# isolator.net
KiCad netlist of a schematic drawn in EAGLE
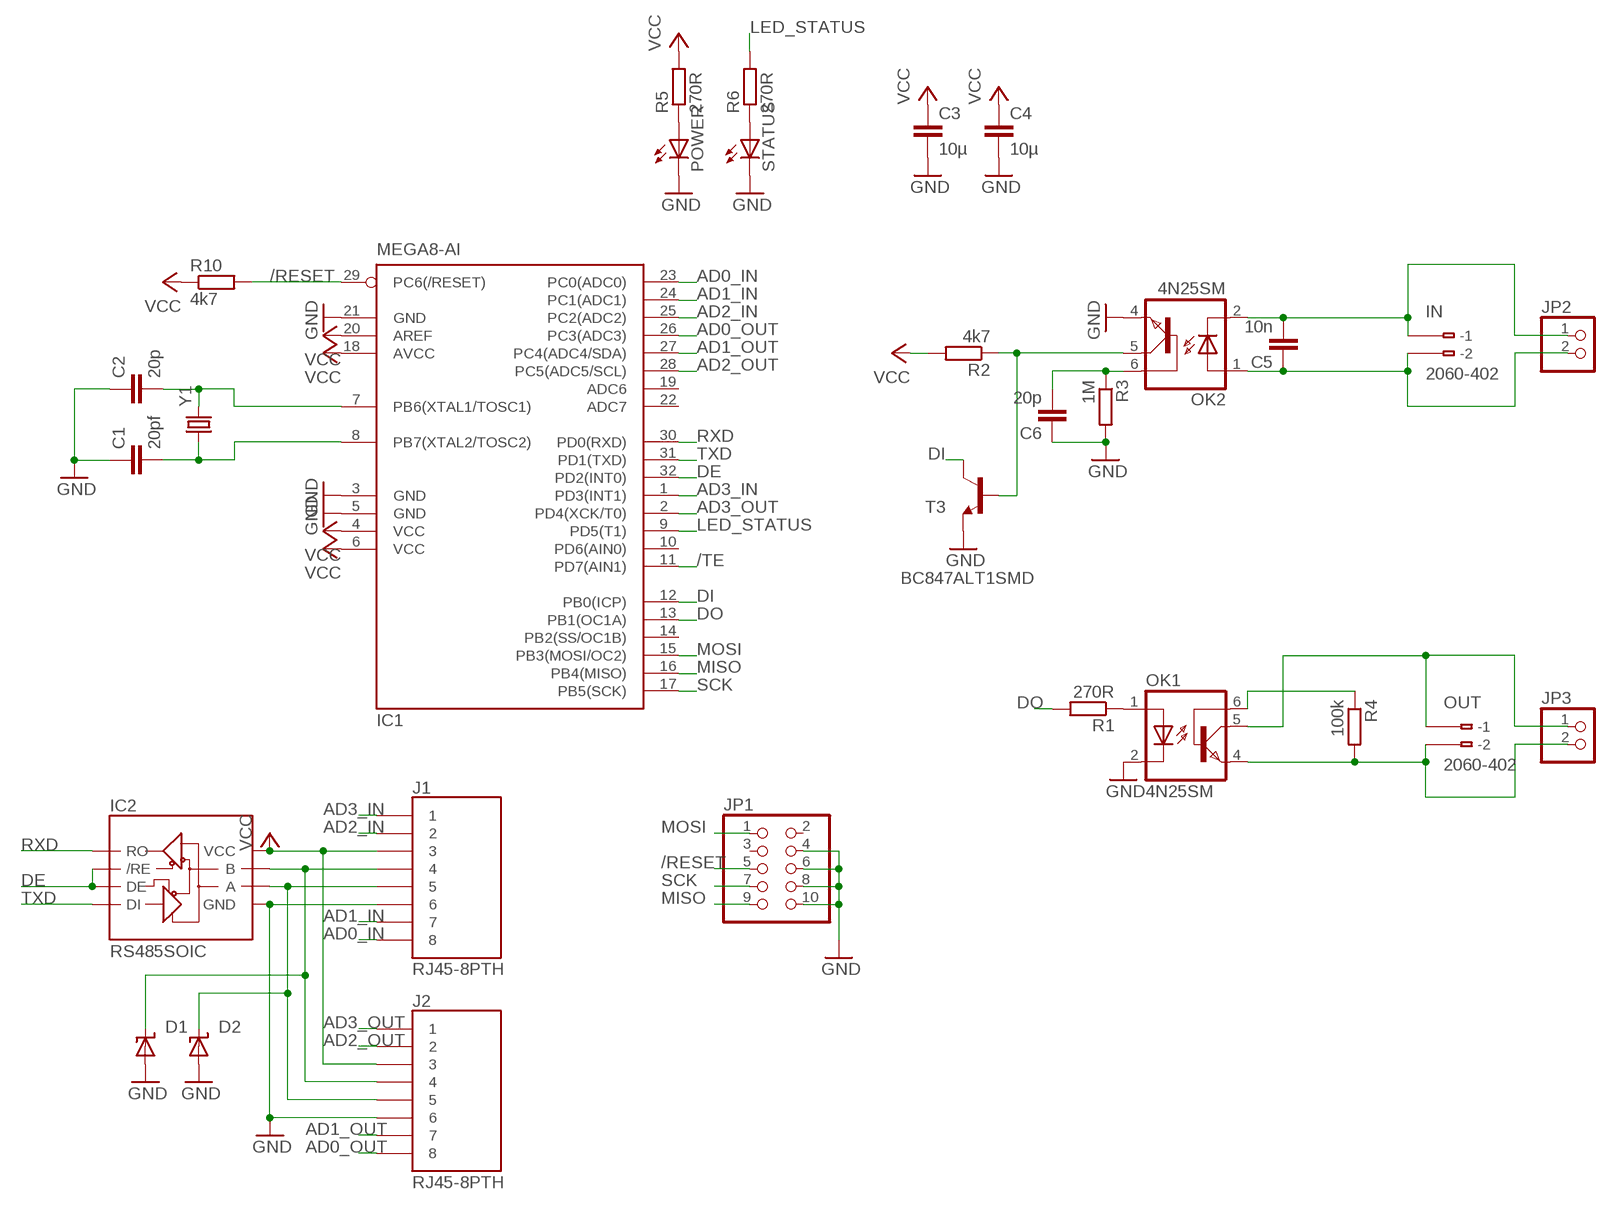
[diagram p0: schematic, sheet 1]

(export (version "E")
  (design (tool "Eeschema 10.0.6"))
  (components
    (comp (ref "C1")
      (value "20pf")
      (footprint "eagle-import:C0805")
      (libsource (lib "eagle-import") (part "C-EUC0805"))
    )
    (comp (ref "C2")
      (value "20p")
      (footprint "eagle-import:C0805")
      (libsource (lib "eagle-import") (part "C-EUC0805"))
    )
    (comp (ref "C3")
      (value "10µ")
      (footprint "eagle-import:C0805")
      (libsource (lib "eagle-import") (part "C-EUC0805"))
    )
    (comp (ref "C4")
      (value "10µ")
      (footprint "eagle-import:C0805")
      (libsource (lib "eagle-import") (part "C-EUC0805"))
    )
    (comp (ref "C5")
      (value "10n")
      (footprint "eagle-import:C0805")
      (libsource (lib "eagle-import") (part "C-EUC0805"))
    )
    (comp (ref "C6")
      (value "20p")
      (footprint "eagle-import:C0805")
      (libsource (lib "eagle-import") (part "C-EUC0805"))
    )
    (comp (ref "D1")
      (value "SUPPRESSOR-SMBJ")
      (footprint "eagle-import:SMBJ")
      (libsource (lib "eagle-import") (part "SUPPRESSOR-SMBJ"))
    )
    (comp (ref "D2")
      (value "SUPPRESSOR-SMBJ")
      (footprint "eagle-import:SMBJ")
      (libsource (lib "eagle-import") (part "SUPPRESSOR-SMBJ"))
    )
    (comp (ref "IC1")
      (value "MEGA8-AI")
      (footprint "eagle-import:TQFP32-08")
      (fields (field (name "MPN") "ATMEGA8-16AU"))
      (libsource (lib "eagle-import") (part "MEGA8-AI"))
    )
    (comp (ref "IC2")
      (value "RS485SOIC")
      (footprint "eagle-import:SO08")
      (libsource (lib "eagle-import") (part "RS485SOIC"))
    )
    (comp (ref "IN")
      (value "2060-402")
      (footprint "eagle-import:2060-402")
      (libsource (lib "eagle-import") (part "2060-402"))
    )
    (comp (ref "J1")
      (value "RJ45-8PTH")
      (footprint "eagle-import:RJ45-8")
      (libsource (lib "eagle-import") (part "RJ45-8PTH"))
    )
    (comp (ref "J2")
      (value "RJ45-8PTH")
      (footprint "eagle-import:RJ45-8")
      (libsource (lib "eagle-import") (part "RJ45-8PTH"))
    )
    (comp (ref "JP1")
      (value "PINHD-2X5")
      (footprint "eagle-import:2X05")
      (libsource (lib "eagle-import") (part "PINHD-2X5"))
    )
    (comp (ref "JP2")
      (value "PINHD-1X2")
      (footprint "eagle-import:1X02")
      (libsource (lib "eagle-import") (part "PINHD-1X2"))
    )
    (comp (ref "JP3")
      (value "PINHD-1X2")
      (footprint "eagle-import:1X02")
      (libsource (lib "eagle-import") (part "PINHD-1X2"))
    )
    (comp (ref "OK1")
      (value "4N25SM")
      (footprint "eagle-import:DIL6-SMD")
      (fields (field (name "MF") "FAIRCHILD SEMICONDUCTOR"))
      (libsource (lib "eagle-import") (part "4N?MS25"))
    )
    (comp (ref "OK2")
      (value "4N25SM")
      (footprint "eagle-import:DIL6-SMD")
      (fields (field (name "MF") "FAIRCHILD SEMICONDUCTOR"))
      (libsource (lib "eagle-import") (part "4N?MS25"))
    )
    (comp (ref "OUT")
      (value "2060-402")
      (footprint "eagle-import:2060-402")
      (libsource (lib "eagle-import") (part "2060-402"))
    )
    (comp (ref "POWER")
      (value "LEDCHIP-LED0805")
      (footprint "eagle-import:CHIP-LED0805")
      (libsource (lib "eagle-import") (part "LEDCHIP-LED0805"))
    )
    (comp (ref "R1")
      (value "270R")
      (footprint "eagle-import:M0805")
      (libsource (lib "eagle-import") (part "R-EU_M0805"))
    )
    (comp (ref "R2")
      (value "4k7")
      (footprint "eagle-import:M0805")
      (libsource (lib "eagle-import") (part "R-EU_M0805"))
    )
    (comp (ref "R3")
      (value "1M")
      (footprint "eagle-import:M0805")
      (libsource (lib "eagle-import") (part "R-EU_M0805"))
    )
    (comp (ref "R4")
      (value "100k")
      (footprint "eagle-import:M0805")
      (libsource (lib "eagle-import") (part "R-EU_M0805"))
    )
    (comp (ref "R5")
      (value "270R")
      (footprint "eagle-import:M0805")
      (libsource (lib "eagle-import") (part "R-EU_M0805"))
    )
    (comp (ref "R6")
      (value "270R")
      (footprint "eagle-import:M0805")
      (libsource (lib "eagle-import") (part "R-EU_M0805"))
    )
    (comp (ref "R10")
      (value "4k7")
      (footprint "eagle-import:M0805")
      (libsource (lib "eagle-import") (part "R-EU_M0805"))
    )
    (comp (ref "STATUS")
      (value "LEDCHIP-LED0805")
      (footprint "eagle-import:CHIP-LED0805")
      (libsource (lib "eagle-import") (part "LEDCHIP-LED0805"))
    )
    (comp (ref "T3")
      (value "BC847ALT1SMD")
      (footprint "eagle-import:SOT23")
      (libsource (lib "eagle-import") (part "BC847SMDALT1"))
    )
    (comp (ref "Y1")
      (value "CRYSTAL10.5X4.8")
      (footprint "eagle-import:CRYSTAL-SMD-10.5X4.8-2PIN")
      (libsource (lib "eagle-import") (part "CRYSTAL10.5X4.8"))
    )
  )
  (nets
    (net (code "1") (name "/AD0_IN") (class "Default")
      (node (ref "IC1") (pin "23") (pinfunction "PC0(ADC0)_23") (pintype "bidirectional"))
      (node (ref "J1") (pin "8") (pinfunction "8_8") (pintype "bidirectional"))
    )
    (net (code "2") (name "/AD0_OUT") (class "Default")
      (node (ref "IC1") (pin "26") (pinfunction "PC3(ADC3)_26") (pintype "bidirectional"))
      (node (ref "J2") (pin "8") (pinfunction "8_8") (pintype "bidirectional"))
    )
    (net (code "3") (name "/AD1_IN") (class "Default")
      (node (ref "IC1") (pin "24") (pinfunction "PC1(ADC1)_24") (pintype "bidirectional"))
      (node (ref "J1") (pin "7") (pinfunction "7_7") (pintype "bidirectional"))
    )
    (net (code "4") (name "/AD1_OUT") (class "Default")
      (node (ref "IC1") (pin "27") (pinfunction "PC4(ADC4/SDA)_27") (pintype "bidirectional"))
      (node (ref "J2") (pin "7") (pinfunction "7_7") (pintype "bidirectional"))
    )
    (net (code "5") (name "/AD2_IN") (class "Default")
      (node (ref "IC1") (pin "25") (pinfunction "PC2(ADC2)_25") (pintype "bidirectional"))
      (node (ref "J1") (pin "2") (pinfunction "2_2") (pintype "bidirectional"))
    )
    (net (code "6") (name "/AD2_OUT") (class "Default")
      (node (ref "IC1") (pin "28") (pinfunction "PC5(ADC5/SCL)_28") (pintype "bidirectional"))
      (node (ref "J2") (pin "2") (pinfunction "2_2") (pintype "bidirectional"))
    )
    (net (code "7") (name "/AD3_IN") (class "Default")
      (node (ref "IC1") (pin "1") (pinfunction "PD3(INT1)_1") (pintype "bidirectional"))
      (node (ref "J1") (pin "1") (pinfunction "1_1") (pintype "bidirectional"))
    )
    (net (code "8") (name "/AD3_OUT") (class "Default")
      (node (ref "IC1") (pin "2") (pinfunction "PD4(XCK/T0)_2") (pintype "bidirectional"))
      (node (ref "J2") (pin "1") (pinfunction "1_1") (pintype "bidirectional"))
    )
    (net (code "9") (name "/DE") (class "Default")
      (node (ref "IC1") (pin "32") (pinfunction "PD2(INT0)_32") (pintype "bidirectional"))
      (node (ref "IC2") (pin "2") (pinfunction "/RE_2") (pintype "bidirectional"))
      (node (ref "IC2") (pin "3") (pinfunction "DE_3") (pintype "bidirectional"))
    )
    (net (code "10") (name "/DI") (class "Default")
      (node (ref "IC1") (pin "12") (pinfunction "PB0(ICP)_12") (pintype "bidirectional"))
      (node (ref "T3") (pin "3") (pinfunction "C_3") (pintype "passive"))
    )
    (net (code "11") (name "/DO") (class "Default")
      (node (ref "IC1") (pin "13") (pinfunction "PB1(OC1A)_13") (pintype "bidirectional"))
      (node (ref "R1") (pin "2") (pinfunction "2_2") (pintype "passive"))
    )
    (net (code "12") (name "/LED_STATUS") (class "Default")
      (node (ref "IC1") (pin "9") (pinfunction "PD5(T1)_9") (pintype "bidirectional"))
      (node (ref "R6") (pin "2") (pinfunction "2_2") (pintype "passive"))
    )
    (net (code "13") (name "/MISO") (class "Default")
      (node (ref "IC1") (pin "16") (pinfunction "PB4(MISO)_16") (pintype "bidirectional"))
      (node (ref "JP1") (pin "9") (pinfunction "9_9") (pintype "passive"))
    )
    (net (code "14") (name "/MOSI") (class "Default")
      (node (ref "IC1") (pin "15") (pinfunction "PB3(MOSI/OC2)_15") (pintype "bidirectional"))
      (node (ref "JP1") (pin "1") (pinfunction "1_1") (pintype "passive"))
    )
    (net (code "15") (name "/RXD") (class "Default")
      (node (ref "IC1") (pin "30") (pinfunction "PD0(RXD)_30") (pintype "bidirectional"))
      (node (ref "IC2") (pin "1") (pinfunction "RO_1") (pintype "bidirectional"))
    )
    (net (code "16") (name "/SCK") (class "Default")
      (node (ref "IC1") (pin "17") (pinfunction "PB5(SCK)_17") (pintype "bidirectional"))
      (node (ref "JP1") (pin "7") (pinfunction "7_7") (pintype "passive"))
    )
    (net (code "17") (name "/TXD") (class "Default")
      (node (ref "IC1") (pin "31") (pinfunction "PD1(TXD)_31") (pintype "bidirectional"))
      (node (ref "IC2") (pin "4") (pinfunction "DI_4") (pintype "bidirectional"))
    )
    (net (code "18") (name "/{slash}RESET") (class "Default")
      (node (ref "IC1") (pin "29") (pinfunction "PC6(/RESET)_29") (pintype "bidirectional"))
      (node (ref "JP1") (pin "5") (pinfunction "5_5") (pintype "passive"))
      (node (ref "R10") (pin "2") (pinfunction "2_2") (pintype "passive"))
    )
    (net (code "19") (name "/{slash}TE") (class "Default")
      (node (ref "IC1") (pin "11") (pinfunction "PD7(AIN1)_11") (pintype "bidirectional"))
    )
    (net (code "20") (name "GND") (class "Default")
      (node (ref "C1") (pin "1") (pinfunction "1_1") (pintype "passive"))
      (node (ref "C2") (pin "1") (pinfunction "1_1") (pintype "passive"))
      (node (ref "C3") (pin "2") (pinfunction "2_2") (pintype "passive"))
      (node (ref "C4") (pin "2") (pinfunction "2_2") (pintype "passive"))
      (node (ref "C6") (pin "1") (pinfunction "1_1") (pintype "passive"))
      (node (ref "D1") (pin "A") (pinfunction "A_A") (pintype "passive"))
      (node (ref "D2") (pin "A") (pinfunction "A_A") (pintype "passive"))
      (node (ref "IC1") (pin "21") (pinfunction "GND_21") (pintype "power_in"))
      (node (ref "IC1") (pin "3") (pinfunction "GND_3") (pintype "power_in"))
      (node (ref "IC1") (pin "5") (pinfunction "GND_5") (pintype "power_in"))
      (node (ref "IC2") (pin "5") (pinfunction "GND_5") (pintype "bidirectional"))
      (node (ref "J1") (pin "6") (pinfunction "6_6") (pintype "bidirectional"))
      (node (ref "J2") (pin "6") (pinfunction "6_6") (pintype "bidirectional"))
      (node (ref "JP1") (pin "10") (pinfunction "10_10") (pintype "passive"))
      (node (ref "JP1") (pin "4") (pinfunction "4_4") (pintype "passive"))
      (node (ref "JP1") (pin "6") (pinfunction "6_6") (pintype "passive"))
      (node (ref "JP1") (pin "8") (pinfunction "8_8") (pintype "passive"))
      (node (ref "OK1") (pin "2") (pinfunction "C_2") (pintype "passive"))
      (node (ref "OK2") (pin "4") (pinfunction "EMI_4") (pintype "passive"))
      (node (ref "POWER") (pin "C") (pinfunction "C_C") (pintype "passive"))
      (node (ref "R3") (pin "2") (pinfunction "2_2") (pintype "passive"))
      (node (ref "STATUS") (pin "C") (pinfunction "C_C") (pintype "passive"))
      (node (ref "T3") (pin "2") (pinfunction "E_2") (pintype "passive"))
    )
    (net (code "21") (name "Net-(IC1-PB6(XTAL1{slash}TOSC1))") (class "Default")
      (node (ref "C2") (pin "2") (pinfunction "2_2") (pintype "passive"))
      (node (ref "IC1") (pin "7") (pinfunction "PB6(XTAL1/TOSC1)_7") (pintype "bidirectional"))
      (node (ref "Y1") (pin "P$2") (pinfunction "2_P$2") (pintype "passive"))
    )
    (net (code "22") (name "Net-(IC1-PB7(XTAL2{slash}TOSC2))") (class "Default")
      (node (ref "C1") (pin "2") (pinfunction "2_2") (pintype "passive"))
      (node (ref "IC1") (pin "8") (pinfunction "PB7(XTAL2/TOSC2)_8") (pintype "bidirectional"))
      (node (ref "Y1") (pin "P$1") (pinfunction "1_P$1") (pintype "passive"))
    )
    (net (code "23") (name "Net-(IC2-A)") (class "Default")
      (node (ref "D2") (pin "C") (pinfunction "C_C") (pintype "passive"))
      (node (ref "IC2") (pin "6") (pinfunction "A_6") (pintype "bidirectional"))
      (node (ref "J1") (pin "5") (pinfunction "5_5") (pintype "bidirectional"))
      (node (ref "J2") (pin "5") (pinfunction "5_5") (pintype "bidirectional"))
    )
    (net (code "24") (name "Net-(IC2-B)") (class "Default")
      (node (ref "D1") (pin "C") (pinfunction "C_C") (pintype "passive"))
      (node (ref "IC2") (pin "7") (pinfunction "B_7") (pintype "bidirectional"))
      (node (ref "J1") (pin "4") (pinfunction "4_4") (pintype "bidirectional"))
      (node (ref "J2") (pin "4") (pinfunction "4_4") (pintype "bidirectional"))
    )
    (net (code "25") (name "Net-(IN-B-1)") (class "Default")
      (node (ref "C5") (pin "2") (pinfunction "2_2") (pintype "passive"))
      (node (ref "IN") (pin "P21") (pinfunction "B-1_P21") (pintype "passive"))
      (node (ref "JP2") (pin "1") (pinfunction "1_1") (pintype "passive"))
      (node (ref "OK2") (pin "2") (pinfunction "C_2") (pintype "passive"))
    )
    (net (code "26") (name "Net-(IN-B-2)") (class "Default")
      (node (ref "C5") (pin "1") (pinfunction "1_1") (pintype "passive"))
      (node (ref "IN") (pin "P22") (pinfunction "B-2_P22") (pintype "passive"))
      (node (ref "JP2") (pin "2") (pinfunction "2_2") (pintype "passive"))
      (node (ref "OK2") (pin "1") (pinfunction "A_1") (pintype "passive"))
    )
    (net (code "27") (name "Net-(OK1-A)") (class "Default")
      (node (ref "OK1") (pin "1") (pinfunction "A_1") (pintype "passive"))
      (node (ref "R1") (pin "1") (pinfunction "1_1") (pintype "passive"))
    )
    (net (code "28") (name "Net-(OK1-BAS)") (class "Default")
      (node (ref "OK1") (pin "6") (pinfunction "BAS_6") (pintype "passive"))
      (node (ref "R4") (pin "1") (pinfunction "1_1") (pintype "passive"))
    )
    (net (code "29") (name "Net-(OK1-COL)") (class "Default")
      (node (ref "JP3") (pin "1") (pinfunction "1_1") (pintype "passive"))
      (node (ref "OK1") (pin "5") (pinfunction "COL_5") (pintype "passive"))
      (node (ref "OUT") (pin "P21") (pinfunction "B-1_P21") (pintype "passive"))
    )
    (net (code "30") (name "Net-(OK1-EMI)") (class "Default")
      (node (ref "JP3") (pin "2") (pinfunction "2_2") (pintype "passive"))
      (node (ref "OK1") (pin "4") (pinfunction "EMI_4") (pintype "passive"))
      (node (ref "OUT") (pin "P22") (pinfunction "B-2_P22") (pintype "passive"))
      (node (ref "R4") (pin "2") (pinfunction "2_2") (pintype "passive"))
    )
    (net (code "31") (name "Net-(OK2-BAS)") (class "Default")
      (node (ref "C6") (pin "2") (pinfunction "2_2") (pintype "passive"))
      (node (ref "OK2") (pin "6") (pinfunction "BAS_6") (pintype "passive"))
      (node (ref "R3") (pin "1") (pinfunction "1_1") (pintype "passive"))
    )
    (net (code "32") (name "Net-(OK2-COL)") (class "Default")
      (node (ref "OK2") (pin "5") (pinfunction "COL_5") (pintype "passive"))
      (node (ref "R2") (pin "1") (pinfunction "1_1") (pintype "passive"))
      (node (ref "T3") (pin "1") (pinfunction "B_1") (pintype "passive"))
    )
    (net (code "33") (name "Net-(POWER-PadA)") (class "Default")
      (node (ref "POWER") (pin "A") (pinfunction "A_A") (pintype "passive"))
      (node (ref "R5") (pin "1") (pinfunction "1_1") (pintype "passive"))
    )
    (net (code "34") (name "Net-(R6-Pad1)") (class "Default")
      (node (ref "R6") (pin "1") (pinfunction "1_1") (pintype "passive"))
      (node (ref "STATUS") (pin "A") (pinfunction "A_A") (pintype "passive"))
    )
    (net (code "35") (name "VCC") (class "Default")
      (node (ref "C3") (pin "1") (pinfunction "1_1") (pintype "passive"))
      (node (ref "C4") (pin "1") (pinfunction "1_1") (pintype "passive"))
      (node (ref "IC1") (pin "18") (pinfunction "AVCC_18") (pintype "power_in"))
      (node (ref "IC1") (pin "20") (pinfunction "AREF_20") (pintype "passive"))
      (node (ref "IC1") (pin "4") (pinfunction "VCC_4") (pintype "power_in"))
      (node (ref "IC1") (pin "6") (pinfunction "VCC_6") (pintype "power_in"))
      (node (ref "IC2") (pin "8") (pinfunction "VCC_8") (pintype "bidirectional"))
      (node (ref "J1") (pin "3") (pinfunction "3_3") (pintype "bidirectional"))
      (node (ref "J2") (pin "3") (pinfunction "3_3") (pintype "bidirectional"))
      (node (ref "R10") (pin "1") (pinfunction "1_1") (pintype "passive"))
      (node (ref "R2") (pin "2") (pinfunction "2_2") (pintype "passive"))
      (node (ref "R5") (pin "2") (pinfunction "2_2") (pintype "passive"))
    )
    (net (code "36") (name "unconnected-(IC1-ADC6-Pad19)") (class "Default")
      (node (ref "IC1") (pin "19") (pinfunction "ADC6_19") (pintype "bidirectional"))
    )
    (net (code "37") (name "unconnected-(IC1-ADC7-Pad22)") (class "Default")
      (node (ref "IC1") (pin "22") (pinfunction "ADC7_22") (pintype "bidirectional"))
    )
    (net (code "38") (name "unconnected-(IC1-PB2(SS{slash}OC1B)-Pad14)") (class "Default")
      (node (ref "IC1") (pin "14") (pinfunction "PB2(SS/OC1B)_14") (pintype "bidirectional"))
    )
    (net (code "39") (name "unconnected-(IC1-PD6(AIN0)-Pad10)") (class "Default")
      (node (ref "IC1") (pin "10") (pinfunction "PD6(AIN0)_10") (pintype "bidirectional"))
    )
    (net (code "40") (name "unconnected-(IN--1-PadP1.1)") (class "Default")
      (node (ref "IN") (pin "P1.1") (pinfunction "-1_P1.1") (pintype "passive"))
    )
    (net (code "41") (name "unconnected-(IN--2-PadP1.2)") (class "Default")
      (node (ref "IN") (pin "P1.2") (pinfunction "-2_P1.2") (pintype "passive"))
    )
    (net (code "42") (name "unconnected-(JP1-Pad2)") (class "Default")
      (node (ref "JP1") (pin "2") (pinfunction "2_2") (pintype "passive"))
    )
    (net (code "43") (name "unconnected-(JP1-Pad3)") (class "Default")
      (node (ref "JP1") (pin "3") (pinfunction "3_3") (pintype "passive"))
    )
    (net (code "44") (name "unconnected-(OUT--1-PadP1.1)") (class "Default")
      (node (ref "OUT") (pin "P1.1") (pinfunction "-1_P1.1") (pintype "passive"))
    )
    (net (code "45") (name "unconnected-(OUT--2-PadP1.2)") (class "Default")
      (node (ref "OUT") (pin "P1.2") (pinfunction "-2_P1.2") (pintype "passive"))
    )
  )
)
